# top_PCB_v1.net
KiCad netlist of a schematic drawn in EAGLE
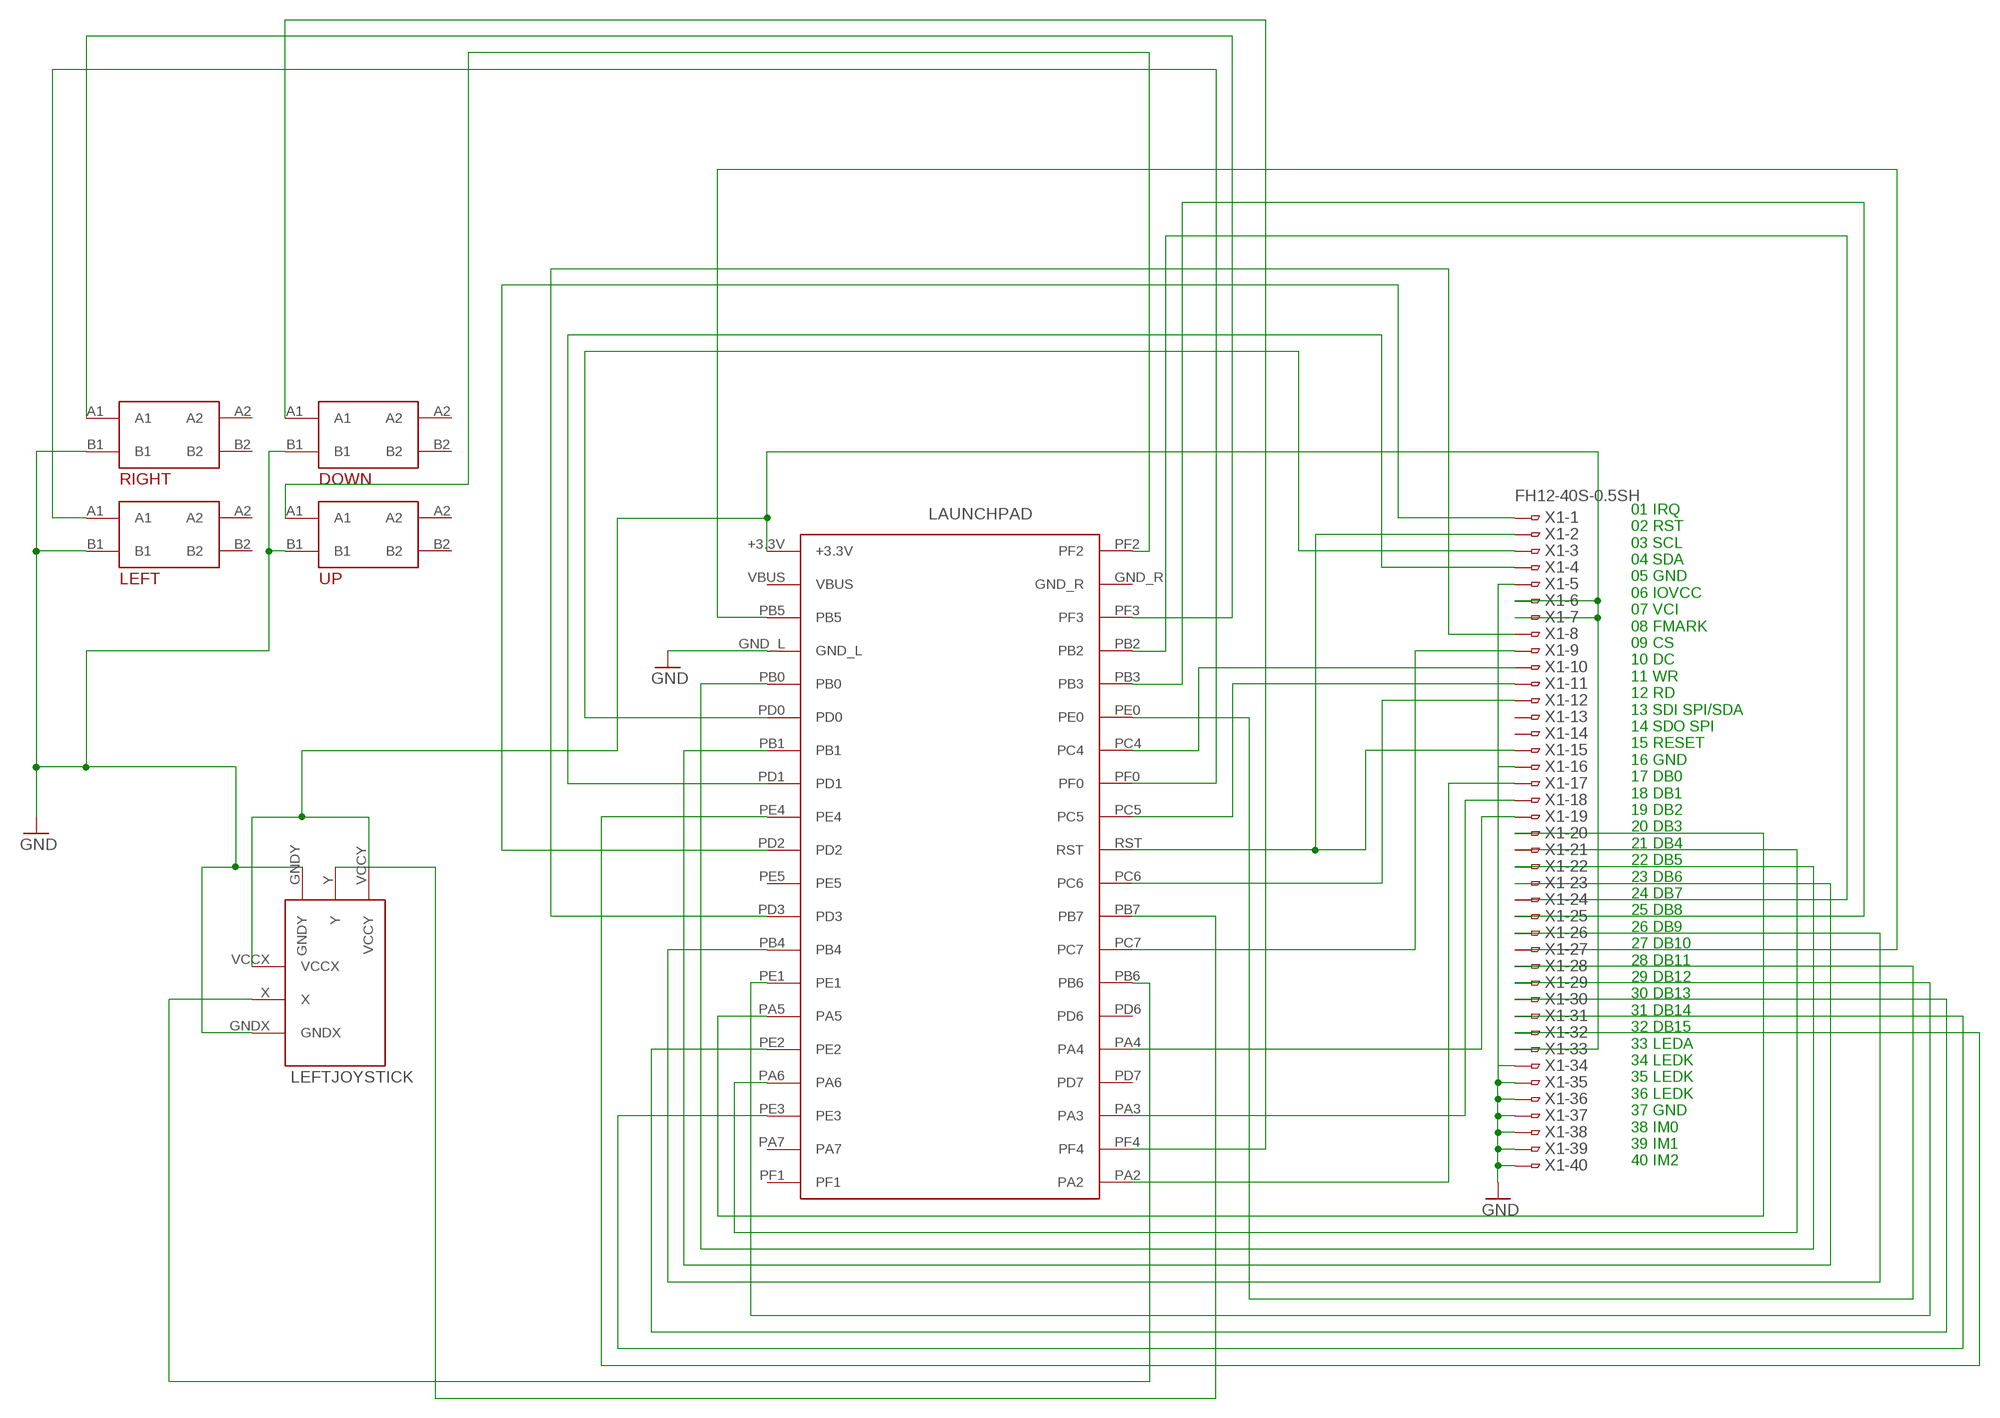
[diagram p0: schematic, sheet 1]

(export (version "E")
  (design (tool "Eeschema 10.0.6"))
  (components
    (comp (ref "DOWN")
      (value "TACTILEBUTTONTHROUGHHOLE")
      (footprint "eagle-import:B3F-40XX-MOD")
      (libsource (lib "eagle-import") (part "TACTILEBUTTONTHROUGHHOLE"))
    )
    (comp (ref "LAUNCHPAD")
      (value "TM4CTM4C")
      (footprint "eagle-import:1_05X2MM")
      (libsource (lib "eagle-import") (part "TM4CTM4C"))
    )
    (comp (ref "LEFT")
      (value "TACTILEBUTTONTHROUGHHOLE")
      (footprint "eagle-import:B3F-40XX-MOD")
      (libsource (lib "eagle-import") (part "TACTILEBUTTONTHROUGHHOLE"))
    )
    (comp (ref "LEFTJOYSTICK")
      (value "JOYSTICKADAFRUIT")
      (footprint "eagle-import:JOYSTICK")
      (libsource (lib "eagle-import") (part "JOYSTICKADAFRUIT"))
    )
    (comp (ref "RIGHT")
      (value "TACTILEBUTTONTHROUGHHOLE")
      (footprint "eagle-import:B3F-40XX-MOD")
      (libsource (lib "eagle-import") (part "TACTILEBUTTONTHROUGHHOLE"))
    )
    (comp (ref "UP")
      (value "TACTILEBUTTONTHROUGHHOLE")
      (footprint "eagle-import:B3F-40XX-MOD")
      (libsource (lib "eagle-import") (part "TACTILEBUTTONTHROUGHHOLE"))
    )
    (comp (ref "X1")
      (value "FH12-40S-0.5SH")
      (footprint "eagle-import:FH12-40S-0.5SH")
      (fields (field (name "MPN") "FH12-40S-0.5SH(55)"))
      (libsource (lib "eagle-import") (part "FH12-40S-0.5SH"))
    )
  )
  (nets
    (net (code "1") (name "/GND_R") (class "Default")
      (node (ref "LAUNCHPAD") (pin "GND_R") (pinfunction "GND_R_GND_R") (pintype "power_in"))
    )
    (net (code "2") (name "/VBUS") (class "Default")
      (node (ref "LAUNCHPAD") (pin "VBUS") (pinfunction "VBUS_VBUS") (pintype "power_in"))
    )
    (net (code "3") (name "GND") (class "Default")
      (node (ref "DOWN") (pin "B1") (pinfunction "B1_B1") (pintype "bidirectional"))
      (node (ref "LAUNCHPAD") (pin "GND_L") (pinfunction "GND_L_GND_L") (pintype "power_in"))
      (node (ref "LEFT") (pin "B1") (pinfunction "B1_B1") (pintype "bidirectional"))
      (node (ref "LEFTJOYSTICK") (pin "GNDX") (pinfunction "GNDX_GNDX") (pintype "bidirectional"))
      (node (ref "LEFTJOYSTICK") (pin "GNDY") (pinfunction "GNDY_GNDY") (pintype "bidirectional"))
      (node (ref "RIGHT") (pin "B1") (pinfunction "B1_B1") (pintype "bidirectional"))
      (node (ref "UP") (pin "B1") (pinfunction "B1_B1") (pintype "bidirectional"))
      (node (ref "X1") (pin "16") (pinfunction "1_16") (pintype "passive"))
      (node (ref "X1") (pin "34") (pinfunction "1_34") (pintype "passive"))
      (node (ref "X1") (pin "35") (pinfunction "1_35") (pintype "passive"))
      (node (ref "X1") (pin "36") (pinfunction "1_36") (pintype "passive"))
      (node (ref "X1") (pin "37") (pinfunction "1_37") (pintype "passive"))
      (node (ref "X1") (pin "38") (pinfunction "1_38") (pintype "passive"))
      (node (ref "X1") (pin "39") (pinfunction "1_39") (pintype "passive"))
      (node (ref "X1") (pin "40") (pinfunction "1_40") (pintype "passive"))
      (node (ref "X1") (pin "5") (pinfunction "1_5") (pintype "passive"))
    )
    (net (code "4") (name "Net-(DOWN-PadA1)") (class "Default")
      (node (ref "DOWN") (pin "A1") (pinfunction "A1_A1") (pintype "bidirectional"))
      (node (ref "LAUNCHPAD") (pin "PF4") (pinfunction "PF4_PF4") (pintype "bidirectional"))
    )
    (net (code "5") (name "Net-(LAUNCHPAD-PadPB6)") (class "Default")
      (node (ref "LAUNCHPAD") (pin "PB6") (pinfunction "PB6_PB6") (pintype "bidirectional"))
      (node (ref "LEFTJOYSTICK") (pin "X") (pinfunction "X_X") (pintype "bidirectional"))
    )
    (net (code "6") (name "Net-(LAUNCHPAD-PadPB7)") (class "Default")
      (node (ref "LAUNCHPAD") (pin "PB7") (pinfunction "PB7_PB7") (pintype "bidirectional"))
      (node (ref "LEFTJOYSTICK") (pin "Y") (pinfunction "Y_Y") (pintype "bidirectional"))
    )
    (net (code "7") (name "Net-(LAUNCHPAD-PadPD2)") (class "Default")
      (node (ref "LAUNCHPAD") (pin "PD2") (pinfunction "PD2_PD2") (pintype "bidirectional"))
      (node (ref "X1") (pin "1") (pinfunction "1_1") (pintype "passive"))
    )
    (net (code "8") (name "Net-(LAUNCHPAD-PadPF0)") (class "Default")
      (node (ref "LAUNCHPAD") (pin "PF0") (pinfunction "PF0_PF0") (pintype "bidirectional"))
      (node (ref "LEFT") (pin "A1") (pinfunction "A1_A1") (pintype "bidirectional"))
    )
    (net (code "9") (name "Net-(LAUNCHPAD-PadPF2)") (class "Default")
      (node (ref "LAUNCHPAD") (pin "PF2") (pinfunction "PF2_PF2") (pintype "bidirectional"))
      (node (ref "UP") (pin "A1") (pinfunction "A1_A1") (pintype "bidirectional"))
    )
    (net (code "10") (name "Net-(LAUNCHPAD-PadPF3)") (class "Default")
      (node (ref "LAUNCHPAD") (pin "PF3") (pinfunction "PF3_PF3") (pintype "bidirectional"))
      (node (ref "RIGHT") (pin "A1") (pinfunction "A1_A1") (pintype "bidirectional"))
    )
    (net (code "11") (name "Net-(X1AA-1)") (class "Default")
      (node (ref "LAUNCHPAD") (pin "+3.3V") (pinfunction "+3.3V_+3.3V") (pintype "power_in"))
      (node (ref "LEFTJOYSTICK") (pin "VCCX") (pinfunction "VCCX_VCCX") (pintype "bidirectional"))
      (node (ref "LEFTJOYSTICK") (pin "VCCY") (pinfunction "VCCY_VCCY") (pintype "bidirectional"))
      (node (ref "X1") (pin "33") (pinfunction "1_33") (pintype "passive"))
      (node (ref "X1") (pin "6") (pinfunction "1_6") (pintype "passive"))
      (node (ref "X1") (pin "7") (pinfunction "1_7") (pintype "passive"))
    )
    (net (code "12") (name "Net-(X1AH-1)") (class "Default")
      (node (ref "LAUNCHPAD") (pin "PD1") (pinfunction "PD1_PD1") (pintype "bidirectional"))
      (node (ref "X1") (pin "4") (pinfunction "1_4") (pintype "passive"))
    )
    (net (code "13") (name "Net-(X1AM-1)") (class "Default")
      (node (ref "LAUNCHPAD") (pin "PD3") (pinfunction "PD3_PD3") (pintype "bidirectional"))
      (node (ref "X1") (pin "8") (pinfunction "1_8") (pintype "passive"))
    )
    (net (code "14") (name "Net-(X1AN-1)") (class "Default")
      (node (ref "LAUNCHPAD") (pin "PC7") (pinfunction "PC7_PC7") (pintype "bidirectional"))
      (node (ref "X1") (pin "9") (pinfunction "1_9") (pintype "passive"))
    )
    (net (code "15") (name "Net-(X1B-1)") (class "Default")
      (node (ref "LAUNCHPAD") (pin "PC4") (pinfunction "PC4_PC4") (pintype "bidirectional"))
      (node (ref "X1") (pin "10") (pinfunction "1_10") (pintype "passive"))
    )
    (net (code "16") (name "Net-(X1C-1)") (class "Default")
      (node (ref "LAUNCHPAD") (pin "PC5") (pinfunction "PC5_PC5") (pintype "bidirectional"))
      (node (ref "X1") (pin "11") (pinfunction "1_11") (pintype "passive"))
    )
    (net (code "17") (name "Net-(X1D-1)") (class "Default")
      (node (ref "LAUNCHPAD") (pin "PC6") (pinfunction "PC6_PC6") (pintype "bidirectional"))
      (node (ref "X1") (pin "12") (pinfunction "1_12") (pintype "passive"))
    )
    (net (code "18") (name "Net-(X1G-1)") (class "Default")
      (node (ref "LAUNCHPAD") (pin "RST") (pinfunction "RST_RST") (pintype "bidirectional"))
      (node (ref "X1") (pin "15") (pinfunction "1_15") (pintype "passive"))
      (node (ref "X1") (pin "2") (pinfunction "1_2") (pintype "passive"))
    )
    (net (code "19") (name "Net-(X1I-1)") (class "Default")
      (node (ref "LAUNCHPAD") (pin "PA2") (pinfunction "PA2_PA2") (pintype "bidirectional"))
      (node (ref "X1") (pin "17") (pinfunction "1_17") (pintype "passive"))
    )
    (net (code "20") (name "Net-(X1J-1)") (class "Default")
      (node (ref "LAUNCHPAD") (pin "PA3") (pinfunction "PA3_PA3") (pintype "bidirectional"))
      (node (ref "X1") (pin "18") (pinfunction "1_18") (pintype "passive"))
    )
    (net (code "21") (name "Net-(X1K-1)") (class "Default")
      (node (ref "LAUNCHPAD") (pin "PA4") (pinfunction "PA4_PA4") (pintype "bidirectional"))
      (node (ref "X1") (pin "19") (pinfunction "1_19") (pintype "passive"))
    )
    (net (code "22") (name "Net-(X1M-1)") (class "Default")
      (node (ref "LAUNCHPAD") (pin "PA5") (pinfunction "PA5_PA5") (pintype "bidirectional"))
      (node (ref "X1") (pin "20") (pinfunction "1_20") (pintype "passive"))
    )
    (net (code "23") (name "Net-(X1N-1)") (class "Default")
      (node (ref "LAUNCHPAD") (pin "PA6") (pinfunction "PA6_PA6") (pintype "bidirectional"))
      (node (ref "X1") (pin "21") (pinfunction "1_21") (pintype "passive"))
    )
    (net (code "24") (name "Net-(X1O-1)") (class "Default")
      (node (ref "LAUNCHPAD") (pin "PB0") (pinfunction "PB0_PB0") (pintype "bidirectional"))
      (node (ref "X1") (pin "22") (pinfunction "1_22") (pintype "passive"))
    )
    (net (code "25") (name "Net-(X1P-1)") (class "Default")
      (node (ref "LAUNCHPAD") (pin "PB1") (pinfunction "PB1_PB1") (pintype "bidirectional"))
      (node (ref "X1") (pin "23") (pinfunction "1_23") (pintype "passive"))
    )
    (net (code "26") (name "Net-(X1Q-1)") (class "Default")
      (node (ref "LAUNCHPAD") (pin "PB2") (pinfunction "PB2_PB2") (pintype "bidirectional"))
      (node (ref "X1") (pin "24") (pinfunction "1_24") (pintype "passive"))
    )
    (net (code "27") (name "Net-(X1R-1)") (class "Default")
      (node (ref "LAUNCHPAD") (pin "PB3") (pinfunction "PB3_PB3") (pintype "bidirectional"))
      (node (ref "X1") (pin "25") (pinfunction "1_25") (pintype "passive"))
    )
    (net (code "28") (name "Net-(X1S-1)") (class "Default")
      (node (ref "LAUNCHPAD") (pin "PB4") (pinfunction "PB4_PB4") (pintype "bidirectional"))
      (node (ref "X1") (pin "26") (pinfunction "1_26") (pintype "passive"))
    )
    (net (code "29") (name "Net-(X1T-1)") (class "Default")
      (node (ref "LAUNCHPAD") (pin "PB5") (pinfunction "PB5_PB5") (pintype "bidirectional"))
      (node (ref "X1") (pin "27") (pinfunction "1_27") (pintype "passive"))
    )
    (net (code "30") (name "Net-(X1U-1)") (class "Default")
      (node (ref "LAUNCHPAD") (pin "PE0") (pinfunction "PE0_PE0") (pintype "bidirectional"))
      (node (ref "X1") (pin "28") (pinfunction "1_28") (pintype "passive"))
    )
    (net (code "31") (name "Net-(X1V-1)") (class "Default")
      (node (ref "LAUNCHPAD") (pin "PE1") (pinfunction "PE1_PE1") (pintype "bidirectional"))
      (node (ref "X1") (pin "29") (pinfunction "1_29") (pintype "passive"))
    )
    (net (code "32") (name "Net-(X1W-1)") (class "Default")
      (node (ref "LAUNCHPAD") (pin "PD0") (pinfunction "PD0_PD0") (pintype "bidirectional"))
      (node (ref "X1") (pin "3") (pinfunction "1_3") (pintype "passive"))
    )
    (net (code "33") (name "Net-(X1X-1)") (class "Default")
      (node (ref "LAUNCHPAD") (pin "PE2") (pinfunction "PE2_PE2") (pintype "bidirectional"))
      (node (ref "X1") (pin "30") (pinfunction "1_30") (pintype "passive"))
    )
    (net (code "34") (name "Net-(X1Y-1)") (class "Default")
      (node (ref "LAUNCHPAD") (pin "PE3") (pinfunction "PE3_PE3") (pintype "bidirectional"))
      (node (ref "X1") (pin "31") (pinfunction "1_31") (pintype "passive"))
    )
    (net (code "35") (name "Net-(X1Z-1)") (class "Default")
      (node (ref "LAUNCHPAD") (pin "PE4") (pinfunction "PE4_PE4") (pintype "bidirectional"))
      (node (ref "X1") (pin "32") (pinfunction "1_32") (pintype "passive"))
    )
    (net (code "36") (name "unconnected-(DOWN-PadA2)") (class "Default")
      (node (ref "DOWN") (pin "A2") (pinfunction "A2_A2") (pintype "bidirectional"))
    )
    (net (code "37") (name "unconnected-(DOWN-PadB2)") (class "Default")
      (node (ref "DOWN") (pin "B2") (pinfunction "B2_B2") (pintype "bidirectional"))
    )
    (net (code "38") (name "unconnected-(LAUNCHPAD-PadPA7)") (class "Default")
      (node (ref "LAUNCHPAD") (pin "PA7") (pinfunction "PA7_PA7") (pintype "bidirectional"))
    )
    (net (code "39") (name "unconnected-(LAUNCHPAD-PadPD6)") (class "Default")
      (node (ref "LAUNCHPAD") (pin "PD6") (pinfunction "PD6_PD6") (pintype "bidirectional"))
    )
    (net (code "40") (name "unconnected-(LAUNCHPAD-PadPD7)") (class "Default")
      (node (ref "LAUNCHPAD") (pin "PD7") (pinfunction "PD7_PD7") (pintype "bidirectional"))
    )
    (net (code "41") (name "unconnected-(LAUNCHPAD-PadPE5)") (class "Default")
      (node (ref "LAUNCHPAD") (pin "PE5") (pinfunction "PE5_PE5") (pintype "bidirectional"))
    )
    (net (code "42") (name "unconnected-(LAUNCHPAD-PadPF1)") (class "Default")
      (node (ref "LAUNCHPAD") (pin "PF1") (pinfunction "PF1_PF1") (pintype "bidirectional"))
    )
    (net (code "43") (name "unconnected-(LEFT-PadA2)") (class "Default")
      (node (ref "LEFT") (pin "A2") (pinfunction "A2_A2") (pintype "bidirectional"))
    )
    (net (code "44") (name "unconnected-(LEFT-PadB2)") (class "Default")
      (node (ref "LEFT") (pin "B2") (pinfunction "B2_B2") (pintype "bidirectional"))
    )
    (net (code "45") (name "unconnected-(RIGHT-PadA2)") (class "Default")
      (node (ref "RIGHT") (pin "A2") (pinfunction "A2_A2") (pintype "bidirectional"))
    )
    (net (code "46") (name "unconnected-(RIGHT-PadB2)") (class "Default")
      (node (ref "RIGHT") (pin "B2") (pinfunction "B2_B2") (pintype "bidirectional"))
    )
    (net (code "47") (name "unconnected-(UP-PadA2)") (class "Default")
      (node (ref "UP") (pin "A2") (pinfunction "A2_A2") (pintype "bidirectional"))
    )
    (net (code "48") (name "unconnected-(UP-PadB2)") (class "Default")
      (node (ref "UP") (pin "B2") (pinfunction "B2_B2") (pintype "bidirectional"))
    )
    (net (code "49") (name "unconnected-(X1E-1-Pad13)") (class "Default")
      (node (ref "X1") (pin "13") (pinfunction "1_13") (pintype "passive"))
    )
    (net (code "50") (name "unconnected-(X1F-1-Pad14)") (class "Default")
      (node (ref "X1") (pin "14") (pinfunction "1_14") (pintype "passive"))
    )
  )
)
